# RN-52_Breakout.net
KiCad netlist of a schematic drawn in EAGLE
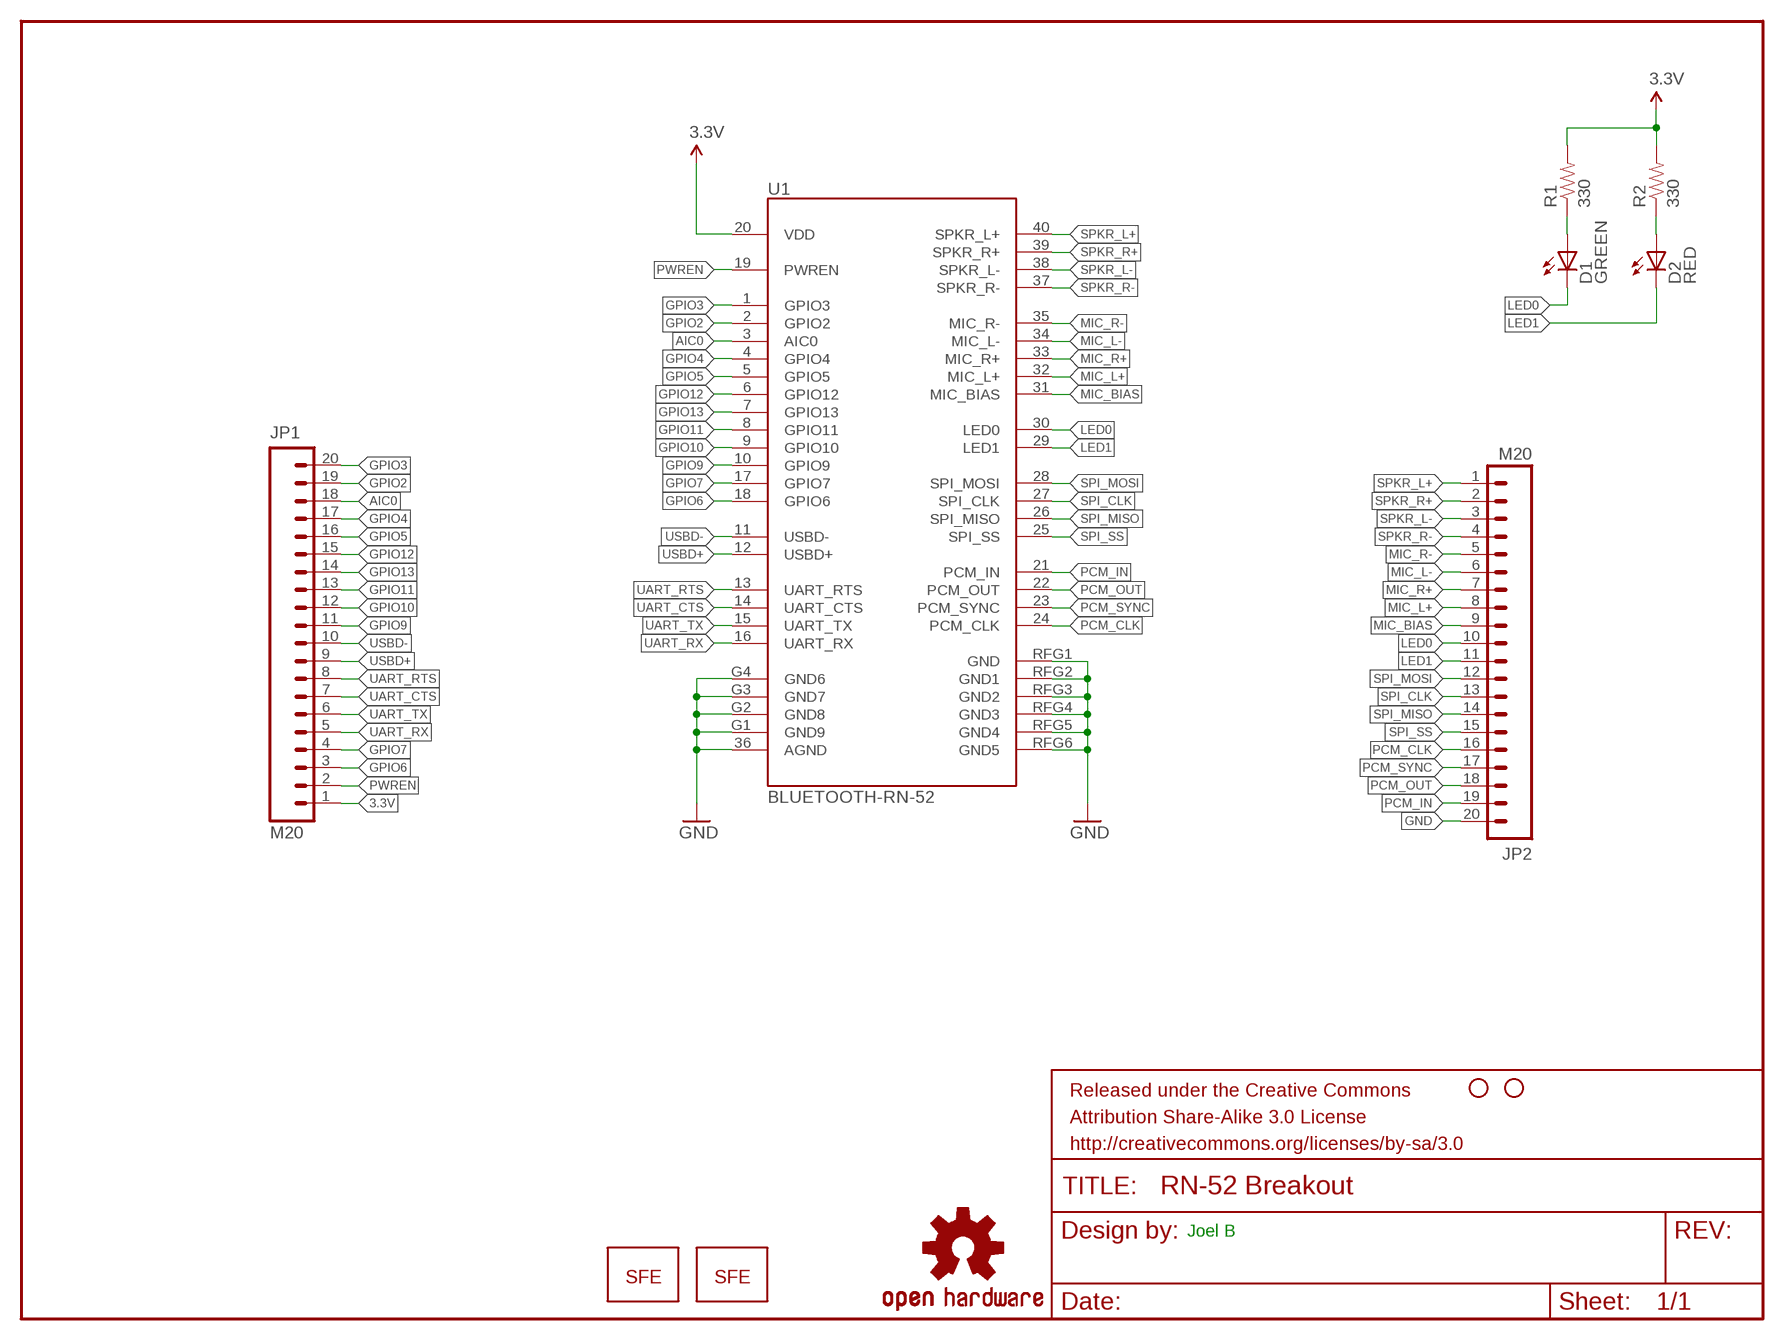
[diagram p0: schematic, sheet 1]

(export (version "E")
  (design (tool "Eeschema 10.0.6"))
  (components
    (comp (ref "D1")
      (value "GREEN")
      (footprint "eagle-import:LED-0603")
      (libsource (lib "eagle-import") (part "LED-GREEN0603"))
    )
    (comp (ref "D2")
      (value "RED")
      (footprint "eagle-import:LED-0603")
      (libsource (lib "eagle-import") (part "LED-RED0603"))
    )
    (comp (ref "FRAME1")
      (value "FRAME-LETTER")
      (footprint "eagle-import:CREATIVE_COMMONS")
      (libsource (lib "eagle-import") (part "FRAME-LETTER"))
    )
    (comp (ref "JP1")
      (value "M20")
      (footprint "eagle-import:1X20")
      (libsource (lib "eagle-import") (part "M20"))
    )
    (comp (ref "JP2")
      (value "M20")
      (footprint "eagle-import:1X20")
      (libsource (lib "eagle-import") (part "M20"))
    )
    (comp (ref "LOGO1")
      (value "OSHW-LOGOS")
      (footprint "eagle-import:OSHW-LOGO-S")
      (libsource (lib "eagle-import") (part "OSHW-LOGOS"))
    )
    (comp (ref "LOGO3")
      (value "LOGO-SFENEW")
      (footprint "eagle-import:SFE-NEW-WEBLOGO")
      (libsource (lib "eagle-import") (part "LOGO-SFENEW"))
    )
    (comp (ref "LOGO4")
      (value "LOGO-SFENW2")
      (footprint "eagle-import:SFE-NEW-WEB")
      (libsource (lib "eagle-import") (part "LOGO-SFENW2"))
    )
    (comp (ref "R1")
      (value "330")
      (footprint "eagle-import:0603-RES")
      (libsource (lib "eagle-import") (part "RESISTOR0603-RES"))
    )
    (comp (ref "R2")
      (value "330")
      (footprint "eagle-import:0603-RES")
      (libsource (lib "eagle-import") (part "RESISTOR0603-RES"))
    )
    (comp (ref "STANDOFF1")
      (value "STAND-OFF")
      (footprint "eagle-import:STAND-OFF")
      (libsource (lib "eagle-import") (part "STAND-OFF"))
    )
    (comp (ref "STANDOFF2")
      (value "STAND-OFF")
      (footprint "eagle-import:STAND-OFF")
      (libsource (lib "eagle-import") (part "STAND-OFF"))
    )
    (comp (ref "U1")
      (value "BLUETOOTH-RN-52")
      (footprint "eagle-import:RN-52")
      (libsource (lib "eagle-import") (part "BLUETOOTH-RN-52"))
    )
  )
  (nets
    (net (code "1") (name "3.3V") (class "Default")
      (node (ref "JP1") (pin "1") (pinfunction "1_1") (pintype "passive"))
      (node (ref "R1") (pin "2") (pinfunction "2_2") (pintype "passive"))
      (node (ref "R2") (pin "2") (pinfunction "2_2") (pintype "passive"))
      (node (ref "U1") (pin "20") (pinfunction "VDD_20") (pintype "bidirectional"))
    )
    (net (code "2") (name "AIC0") (class "Default")
      (node (ref "JP1") (pin "18") (pinfunction "18_18") (pintype "passive"))
      (node (ref "U1") (pin "3") (pinfunction "AIC0_3") (pintype "bidirectional"))
    )
    (net (code "3") (name "GND") (class "Default")
      (node (ref "JP2") (pin "20") (pinfunction "20_20") (pintype "passive"))
      (node (ref "U1") (pin "36") (pinfunction "AGND_36") (pintype "bidirectional"))
      (node (ref "U1") (pin "G1") (pinfunction "GND9_G1") (pintype "bidirectional"))
      (node (ref "U1") (pin "G2") (pinfunction "GND8_G2") (pintype "bidirectional"))
      (node (ref "U1") (pin "G3") (pinfunction "GND7_G3") (pintype "bidirectional"))
      (node (ref "U1") (pin "G4") (pinfunction "GND6_G4") (pintype "bidirectional"))
      (node (ref "U1") (pin "RFG1") (pinfunction "GND_RFG1") (pintype "bidirectional"))
      (node (ref "U1") (pin "RFG2") (pinfunction "GND1_RFG2") (pintype "bidirectional"))
      (node (ref "U1") (pin "RFG3") (pinfunction "GND2_RFG3") (pintype "bidirectional"))
      (node (ref "U1") (pin "RFG4") (pinfunction "GND3_RFG4") (pintype "bidirectional"))
      (node (ref "U1") (pin "RFG5") (pinfunction "GND4_RFG5") (pintype "bidirectional"))
      (node (ref "U1") (pin "RFG6") (pinfunction "GND5_RFG6") (pintype "bidirectional"))
    )
    (net (code "4") (name "GPIO2") (class "Default")
      (node (ref "JP1") (pin "19") (pinfunction "19_19") (pintype "passive"))
      (node (ref "U1") (pin "2") (pinfunction "GPIO2_2") (pintype "bidirectional"))
    )
    (net (code "5") (name "GPIO3") (class "Default")
      (node (ref "JP1") (pin "20") (pinfunction "20_20") (pintype "passive"))
      (node (ref "U1") (pin "1") (pinfunction "GPIO3_1") (pintype "bidirectional"))
    )
    (net (code "6") (name "GPIO4") (class "Default")
      (node (ref "JP1") (pin "17") (pinfunction "17_17") (pintype "passive"))
      (node (ref "U1") (pin "4") (pinfunction "GPIO4_4") (pintype "bidirectional"))
    )
    (net (code "7") (name "GPIO5") (class "Default")
      (node (ref "JP1") (pin "16") (pinfunction "16_16") (pintype "passive"))
      (node (ref "U1") (pin "5") (pinfunction "GPIO5_5") (pintype "bidirectional"))
    )
    (net (code "8") (name "GPIO6") (class "Default")
      (node (ref "JP1") (pin "3") (pinfunction "3_3") (pintype "passive"))
      (node (ref "U1") (pin "18") (pinfunction "GPIO6_18") (pintype "bidirectional"))
    )
    (net (code "9") (name "GPIO7") (class "Default")
      (node (ref "JP1") (pin "4") (pinfunction "4_4") (pintype "passive"))
      (node (ref "U1") (pin "17") (pinfunction "GPIO7_17") (pintype "bidirectional"))
    )
    (net (code "10") (name "GPIO9") (class "Default")
      (node (ref "JP1") (pin "11") (pinfunction "11_11") (pintype "passive"))
      (node (ref "U1") (pin "10") (pinfunction "GPIO9_10") (pintype "bidirectional"))
    )
    (net (code "11") (name "GPIO10") (class "Default")
      (node (ref "JP1") (pin "12") (pinfunction "12_12") (pintype "passive"))
      (node (ref "U1") (pin "9") (pinfunction "GPIO10_9") (pintype "bidirectional"))
    )
    (net (code "12") (name "GPIO11") (class "Default")
      (node (ref "JP1") (pin "13") (pinfunction "13_13") (pintype "passive"))
      (node (ref "U1") (pin "8") (pinfunction "GPIO11_8") (pintype "bidirectional"))
    )
    (net (code "13") (name "GPIO12") (class "Default")
      (node (ref "JP1") (pin "15") (pinfunction "15_15") (pintype "passive"))
      (node (ref "U1") (pin "6") (pinfunction "GPIO12_6") (pintype "bidirectional"))
    )
    (net (code "14") (name "GPIO13") (class "Default")
      (node (ref "JP1") (pin "14") (pinfunction "14_14") (pintype "passive"))
      (node (ref "U1") (pin "7") (pinfunction "GPIO13_7") (pintype "bidirectional"))
    )
    (net (code "15") (name "LED0") (class "Default")
      (node (ref "D1") (pin "C") (pinfunction "C_C") (pintype "passive"))
      (node (ref "JP2") (pin "10") (pinfunction "10_10") (pintype "passive"))
      (node (ref "U1") (pin "30") (pinfunction "LED0_30") (pintype "bidirectional"))
    )
    (net (code "16") (name "LED1") (class "Default")
      (node (ref "D2") (pin "C") (pinfunction "C_C") (pintype "passive"))
      (node (ref "JP2") (pin "11") (pinfunction "11_11") (pintype "passive"))
      (node (ref "U1") (pin "29") (pinfunction "LED1_29") (pintype "bidirectional"))
    )
    (net (code "17") (name "MIC_BIAS") (class "Default")
      (node (ref "JP2") (pin "9") (pinfunction "9_9") (pintype "passive"))
      (node (ref "U1") (pin "31") (pinfunction "MIC_BIAS_31") (pintype "bidirectional"))
    )
    (net (code "18") (name "MIC_L+") (class "Default")
      (node (ref "JP2") (pin "8") (pinfunction "8_8") (pintype "passive"))
      (node (ref "U1") (pin "32") (pinfunction "MIC_L+_32") (pintype "bidirectional"))
    )
    (net (code "19") (name "MIC_L-") (class "Default")
      (node (ref "JP2") (pin "6") (pinfunction "6_6") (pintype "passive"))
      (node (ref "U1") (pin "34") (pinfunction "MIC_L-_34") (pintype "bidirectional"))
    )
    (net (code "20") (name "MIC_R+") (class "Default")
      (node (ref "JP2") (pin "7") (pinfunction "7_7") (pintype "passive"))
      (node (ref "U1") (pin "33") (pinfunction "MIC_R+_33") (pintype "bidirectional"))
    )
    (net (code "21") (name "MIC_R-") (class "Default")
      (node (ref "JP2") (pin "5") (pinfunction "5_5") (pintype "passive"))
      (node (ref "U1") (pin "35") (pinfunction "MIC_R-_35") (pintype "bidirectional"))
    )
    (net (code "22") (name "Net-(D1-PadA)") (class "Default")
      (node (ref "D1") (pin "A") (pinfunction "A_A") (pintype "passive"))
      (node (ref "R1") (pin "1") (pinfunction "1_1") (pintype "passive"))
    )
    (net (code "23") (name "Net-(D2-PadA)") (class "Default")
      (node (ref "D2") (pin "A") (pinfunction "A_A") (pintype "passive"))
      (node (ref "R2") (pin "1") (pinfunction "1_1") (pintype "passive"))
    )
    (net (code "24") (name "PCM_CLK") (class "Default")
      (node (ref "JP2") (pin "16") (pinfunction "16_16") (pintype "passive"))
      (node (ref "U1") (pin "24") (pinfunction "PCM_CLK_24") (pintype "bidirectional"))
    )
    (net (code "25") (name "PCM_IN") (class "Default")
      (node (ref "JP2") (pin "19") (pinfunction "19_19") (pintype "passive"))
      (node (ref "U1") (pin "21") (pinfunction "PCM_IN_21") (pintype "bidirectional"))
    )
    (net (code "26") (name "PCM_OUT") (class "Default")
      (node (ref "JP2") (pin "18") (pinfunction "18_18") (pintype "passive"))
      (node (ref "U1") (pin "22") (pinfunction "PCM_OUT_22") (pintype "bidirectional"))
    )
    (net (code "27") (name "PCM_SYNC") (class "Default")
      (node (ref "JP2") (pin "17") (pinfunction "17_17") (pintype "passive"))
      (node (ref "U1") (pin "23") (pinfunction "PCM_SYNC_23") (pintype "bidirectional"))
    )
    (net (code "28") (name "PWREN") (class "Default")
      (node (ref "JP1") (pin "2") (pinfunction "2_2") (pintype "passive"))
      (node (ref "U1") (pin "19") (pinfunction "PWREN_19") (pintype "bidirectional"))
    )
    (net (code "29") (name "SPI_CLK") (class "Default")
      (node (ref "JP2") (pin "13") (pinfunction "13_13") (pintype "passive"))
      (node (ref "U1") (pin "27") (pinfunction "SPI_CLK_27") (pintype "bidirectional"))
    )
    (net (code "30") (name "SPI_MISO") (class "Default")
      (node (ref "JP2") (pin "14") (pinfunction "14_14") (pintype "passive"))
      (node (ref "U1") (pin "26") (pinfunction "SPI_MISO_26") (pintype "bidirectional"))
    )
    (net (code "31") (name "SPI_MOSI") (class "Default")
      (node (ref "JP2") (pin "12") (pinfunction "12_12") (pintype "passive"))
      (node (ref "U1") (pin "28") (pinfunction "SPI_MOSI_28") (pintype "bidirectional"))
    )
    (net (code "32") (name "SPI_SS") (class "Default")
      (node (ref "JP2") (pin "15") (pinfunction "15_15") (pintype "passive"))
      (node (ref "U1") (pin "25") (pinfunction "SPI_SS_25") (pintype "bidirectional"))
    )
    (net (code "33") (name "SPKR_L+") (class "Default")
      (node (ref "JP2") (pin "1") (pinfunction "1_1") (pintype "passive"))
      (node (ref "U1") (pin "40") (pinfunction "SPKR_L+_40") (pintype "bidirectional"))
    )
    (net (code "34") (name "SPKR_L-") (class "Default")
      (node (ref "JP2") (pin "3") (pinfunction "3_3") (pintype "passive"))
      (node (ref "U1") (pin "38") (pinfunction "SPKR_L-_38") (pintype "bidirectional"))
    )
    (net (code "35") (name "SPKR_R+") (class "Default")
      (node (ref "JP2") (pin "2") (pinfunction "2_2") (pintype "passive"))
      (node (ref "U1") (pin "39") (pinfunction "SPKR_R+_39") (pintype "bidirectional"))
    )
    (net (code "36") (name "SPKR_R-") (class "Default")
      (node (ref "JP2") (pin "4") (pinfunction "4_4") (pintype "passive"))
      (node (ref "U1") (pin "37") (pinfunction "SPKR_R-_37") (pintype "bidirectional"))
    )
    (net (code "37") (name "UART_CTS") (class "Default")
      (node (ref "JP1") (pin "7") (pinfunction "7_7") (pintype "passive"))
      (node (ref "U1") (pin "14") (pinfunction "UART_CTS_14") (pintype "bidirectional"))
    )
    (net (code "38") (name "UART_RTS") (class "Default")
      (node (ref "JP1") (pin "8") (pinfunction "8_8") (pintype "passive"))
      (node (ref "U1") (pin "13") (pinfunction "UART_RTS_13") (pintype "bidirectional"))
    )
    (net (code "39") (name "UART_RX") (class "Default")
      (node (ref "JP1") (pin "5") (pinfunction "5_5") (pintype "passive"))
      (node (ref "U1") (pin "16") (pinfunction "UART_RX_16") (pintype "bidirectional"))
    )
    (net (code "40") (name "UART_TX") (class "Default")
      (node (ref "JP1") (pin "6") (pinfunction "6_6") (pintype "passive"))
      (node (ref "U1") (pin "15") (pinfunction "UART_TX_15") (pintype "bidirectional"))
    )
    (net (code "41") (name "USBD+") (class "Default")
      (node (ref "JP1") (pin "9") (pinfunction "9_9") (pintype "passive"))
      (node (ref "U1") (pin "12") (pinfunction "USBD+_12") (pintype "bidirectional"))
    )
    (net (code "42") (name "USBD-") (class "Default")
      (node (ref "JP1") (pin "10") (pinfunction "10_10") (pintype "passive"))
      (node (ref "U1") (pin "11") (pinfunction "USBD-_11") (pintype "bidirectional"))
    )
  )
)
